# zasilanie.net
KiCad netlist of a schematic drawn in Altium Designer
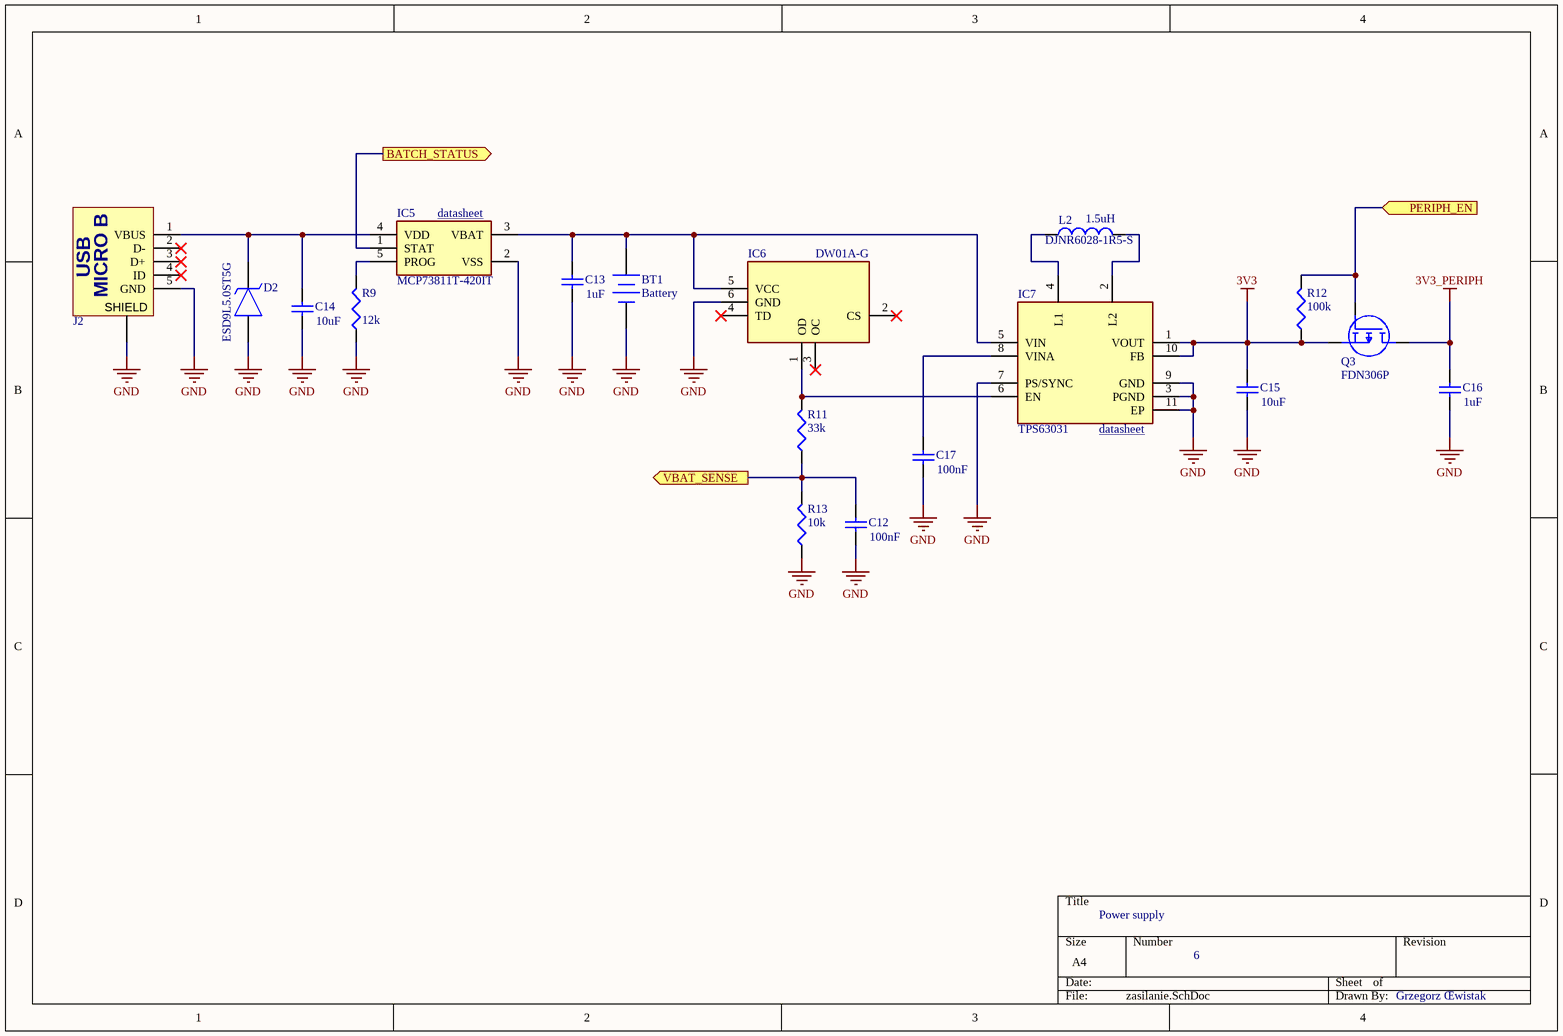
[diagram p0: zasilanie.SchDoc]

(export (version "E")
  (design (tool "Eeschema 10.0.6"))
  (components
    (comp (ref "BT1")
      (value "Battery")
      (footprint "BAT_PAD")
      (description "Multicell Battery")
      (fields (field (name "PUBLISHER") "Altium Limited"))
      (libsource (lib "Miscellaneous Devices") (part "Battery"))
    )
    (comp (ref "C12")
      (value "100nF")
      (footprint "C0805")
      (description "Capacitor")
      (fields (field (name "Comment") "Cap") (field (name "PUBLISHER") "Altium Limited"))
      (libsource (lib "Miscellaneous Devices") (part "Cap"))
    )
    (comp (ref "C13")
      (value "1uF")
      (footprint "cap-0603")
      (description "Capacitor")
      (fields (field (name "Comment") "Cap") (field (name "PUBLISHER") "Altium Limited"))
      (libsource (lib "Miscellaneous Devices") (part "Cap"))
    )
    (comp (ref "C14")
      (value "10uF")
      (footprint "cap-0603")
      (description "Capacitor")
      (fields (field (name "Comment") "Cap") (field (name "PUBLISHER") "Altium Limited"))
      (libsource (lib "Miscellaneous Devices") (part "Cap"))
    )
    (comp (ref "C15")
      (value "10uF")
      (footprint "cap-0603")
      (description "Capacitor")
      (fields (field (name "Comment") "Cap") (field (name "PUBLISHER") "Altium Limited"))
      (libsource (lib "Miscellaneous Devices") (part "Cap"))
    )
    (comp (ref "C16")
      (value "1uF")
      (footprint "cap-0603")
      (description "Capacitor")
      (fields (field (name "Comment") "Cap") (field (name "PUBLISHER") "Altium Limited"))
      (libsource (lib "Miscellaneous Devices") (part "Cap"))
    )
    (comp (ref "C17")
      (value "100nF")
      (footprint "C0805")
      (description "Capacitor")
      (fields (field (name "Comment") "Cap") (field (name "PUBLISHER") "Altium Limited"))
      (libsource (lib "Miscellaneous Devices") (part "Cap"))
    )
    (comp (ref "D2")
      (value "ESD9L5.0ST5G")
      (footprint "SODFL1006X40N")
      (description "Transil")
      (fields (field (name "MOUSER PART NUMBER") "863-ESD9L5.0ST5G"))
      (libsource (lib "lib") (part "ESD9L5.0ST5G"))
    )
    (comp (ref "IC5")
      (value "MCP73811T-420IT")
      (footprint "SOT95P270X145-5N")
      (description "Integrated Circuit")
      (fields
        (field (name "MANUFACTURER_PART_NUMBER") "MCP73831T-5ACI/OT")
        (field (name "MOUSER PART NUMBER") "579-MCP73831T5ACIOT")
      )
      (libsource (lib "lib") (part "MCP73831T"))
    )
    (comp (ref "IC6")
      (value "DW01A-G")
      (footprint "SOT95P280X135-6N")
      (description "Integrated Circuit")
      (libsource (lib "lib") (part "DW01A-G"))
    )
    (comp (ref "IC7")
      (value "TPS63031")
      (footprint "SON50P250X250X80-11N-D")
      (description "TPS63031 buck-boost 3v3")
      (fields
        (field (name "MANUFACTURER_PART_NUMBER") "TPS63031DSKT")
        (field (name "MOUSER PART NUMBER") "595-TPS63031DSKT")
      )
      (libsource (lib "lib") (part "TPS63031DSKT"))
    )
    (comp (ref "J2")
      (value "Micro USB")
      (footprint "101181930001LF")
      (description "model 10118193-0001LF amphenol")
      (fields
        (field (name "MANUFACTURER_PART_NUMBER") "10118193-0001LF")
        (field (name "MOUSER PART NUMBER") "649-10118193-0001LF")
      )
      (libsource (lib "lib") (part "USB-10118193-0001LF"))
    )
    (comp (ref "L2")
      (value "DJNR6028-1R5-S")
      (footprint "DJNR6028-1R5-S")
      (fields (field (name "ALTIUM_VALUE") "1.5uH") (field (name "PUBLISHER") "Altium Limited"))
      (libsource (lib "Miscellaneous Devices") (part "Inductor"))
    )
    (comp (ref "Q3")
      (value "FDN306P")
      (footprint "SOT95P237X112-3N")
      (description "MOSFET (P-Channel)")
      (fields (field (name "MOUSER PART NUMBER") "512-FDN306P"))
      (libsource (lib "lib") (part "FDN306P"))
    )
    (comp (ref "R9")
      (value "12k")
      (footprint "R0603")
      (description "Resistor")
      (fields (field (name "Comment") "Res3") (field (name "PUBLISHER") "Altium Limited"))
      (libsource (lib "Miscellaneous Devices") (part "Res3"))
    )
    (comp (ref "R11")
      (value "33k")
      (footprint "R0603")
      (description "Resistor")
      (fields (field (name "Comment") "Res3") (field (name "PUBLISHER") "Altium Limited"))
      (libsource (lib "Miscellaneous Devices") (part "Res3"))
    )
    (comp (ref "R12")
      (value "100k")
      (footprint "R0603")
      (description "Resistor")
      (fields (field (name "Comment") "Res3") (field (name "PUBLISHER") "Altium Limited"))
      (libsource (lib "Miscellaneous Devices") (part "Res3"))
    )
    (comp (ref "R13")
      (value "10k")
      (footprint "R0603")
      (description "Resistor")
      (fields (field (name "Comment") "Res3") (field (name "PUBLISHER") "Altium Limited"))
      (libsource (lib "Miscellaneous Devices") (part "Res3"))
    )
  )
  (nets
    (net (code "1") (name "/BATCH_STATUS") (class "Default")
      (node (ref "IC5") (pin "1") (pinfunction "STAT_1") (pintype "passive"))
    )
    (net (code "2") (name "/PERIPH_EN") (class "Default")
      (node (ref "Q3") (pin "1") (pinfunction "G_1") (pintype "passive"))
      (node (ref "R12") (pin "1") (pinfunction "1_1") (pintype "passive"))
    )
    (net (code "3") (name "/VBAT_SENSE") (class "Default")
      (node (ref "C12") (pin "2") (pinfunction "2_2") (pintype "passive"))
      (node (ref "R11") (pin "2") (pinfunction "2_2") (pintype "passive"))
      (node (ref "R13") (pin "1") (pinfunction "1_1") (pintype "passive"))
    )
    (net (code "4") (name "3V3") (class "Default")
      (node (ref "C15") (pin "2") (pinfunction "2_2") (pintype "passive"))
      (node (ref "IC7") (pin "1") (pinfunction "VOUT_1") (pintype "passive"))
      (node (ref "IC7") (pin "10") (pinfunction "FB_10") (pintype "passive"))
      (node (ref "Q3") (pin "2") (pinfunction "S_2") (pintype "passive"))
      (node (ref "R12") (pin "2") (pinfunction "2_2") (pintype "passive"))
    )
    (net (code "5") (name "3V3_PERIPH") (class "Default")
      (node (ref "C16") (pin "2") (pinfunction "2_2") (pintype "passive"))
      (node (ref "Q3") (pin "3") (pinfunction "D_3") (pintype "passive"))
    )
    (net (code "6") (name "GND") (class "Default")
      (node (ref "BT1") (pin "2") (pinfunction "-_2") (pintype "passive"))
      (node (ref "C12") (pin "1") (pinfunction "1_1") (pintype "passive"))
      (node (ref "C13") (pin "1") (pinfunction "1_1") (pintype "passive"))
      (node (ref "C14") (pin "1") (pinfunction "1_1") (pintype "passive"))
      (node (ref "C15") (pin "1") (pinfunction "1_1") (pintype "passive"))
      (node (ref "C16") (pin "1") (pinfunction "1_1") (pintype "passive"))
      (node (ref "C17") (pin "1") (pinfunction "1_1") (pintype "passive"))
      (node (ref "D2") (pin "2") (pinfunction "A_2") (pintype "passive"))
      (node (ref "IC5") (pin "2") (pinfunction "VSS_2") (pintype "passive"))
      (node (ref "IC6") (pin "6") (pinfunction "GND_6") (pintype "passive"))
      (node (ref "IC7") (pin "11") (pinfunction "EP_11") (pintype "passive"))
      (node (ref "IC7") (pin "3") (pinfunction "PGND_3") (pintype "passive"))
      (node (ref "IC7") (pin "7") (pinfunction "PS/SYNC_7") (pintype "passive"))
      (node (ref "IC7") (pin "9") (pinfunction "GND_9") (pintype "passive"))
      (node (ref "J2") (pin "5") (pinfunction "GND_5") (pintype "passive"))
      (node (ref "J2") (pin "6") (pinfunction "SHIELD_6") (pintype "passive"))
      (node (ref "R13") (pin "2") (pinfunction "2_2") (pintype "passive"))
      (node (ref "R9") (pin "1") (pinfunction "1_1") (pintype "passive"))
    )
    (net (code "7") (name "Net-(BT1-+)") (class "Default")
      (node (ref "BT1") (pin "1") (pinfunction "+_1") (pintype "passive"))
      (node (ref "C13") (pin "2") (pinfunction "2_2") (pintype "passive"))
      (node (ref "IC5") (pin "3") (pinfunction "VBAT_3") (pintype "passive"))
      (node (ref "IC6") (pin "5") (pinfunction "VCC_5") (pintype "passive"))
      (node (ref "IC7") (pin "5") (pinfunction "VIN_5") (pintype "passive"))
    )
    (net (code "8") (name "Net-(D2-K)") (class "Default")
      (node (ref "C14") (pin "2") (pinfunction "2_2") (pintype "passive"))
      (node (ref "D2") (pin "1") (pinfunction "K_1") (pintype "passive"))
      (node (ref "IC5") (pin "4") (pinfunction "VDD_4") (pintype "passive"))
      (node (ref "J2") (pin "1") (pinfunction "VBUS_1") (pintype "passive"))
    )
    (net (code "9") (name "Net-(IC5-PROG)") (class "Default")
      (node (ref "IC5") (pin "5") (pinfunction "PROG_5") (pintype "passive"))
      (node (ref "R9") (pin "2") (pinfunction "2_2") (pintype "passive"))
    )
    (net (code "10") (name "Net-(IC6-OD)") (class "Default")
      (node (ref "IC6") (pin "1") (pinfunction "OD_1") (pintype "passive"))
      (node (ref "IC7") (pin "6") (pinfunction "EN_6") (pintype "passive"))
      (node (ref "R11") (pin "1") (pinfunction "1_1") (pintype "passive"))
    )
    (net (code "11") (name "Net-(IC7-L1)") (class "Default")
      (node (ref "IC7") (pin "4") (pinfunction "L1_4") (pintype "passive"))
      (node (ref "L2") (pin "1") (pinfunction "1_1") (pintype "passive"))
    )
    (net (code "12") (name "Net-(IC7-L2)") (class "Default")
      (node (ref "IC7") (pin "2") (pinfunction "L2_2") (pintype "passive"))
      (node (ref "L2") (pin "2") (pinfunction "2_2") (pintype "passive"))
    )
    (net (code "13") (name "Net-(IC7-VINA)") (class "Default")
      (node (ref "C17") (pin "2") (pinfunction "2_2") (pintype "passive"))
      (node (ref "IC7") (pin "8") (pinfunction "VINA_8") (pintype "passive"))
    )
    (net (code "14") (name "unconnected-(IC6-CS-Pad2)") (class "Default")
      (node (ref "IC6") (pin "2") (pinfunction "CS_2") (pintype "passive+no_connect"))
    )
    (net (code "15") (name "unconnected-(IC6-OC-Pad3)") (class "Default")
      (node (ref "IC6") (pin "3") (pinfunction "OC_3") (pintype "passive+no_connect"))
    )
    (net (code "16") (name "unconnected-(IC6-TD-Pad4)") (class "Default")
      (node (ref "IC6") (pin "4") (pinfunction "TD_4") (pintype "passive+no_connect"))
    )
    (net (code "17") (name "unconnected-(J2-D+-Pad3)") (class "Default")
      (node (ref "J2") (pin "3") (pinfunction "D+_3") (pintype "passive+no_connect"))
    )
    (net (code "18") (name "unconnected-(J2-D--Pad2)") (class "Default")
      (node (ref "J2") (pin "2") (pinfunction "D-_2") (pintype "passive+no_connect"))
    )
    (net (code "19") (name "unconnected-(J2-ID-Pad4)") (class "Default")
      (node (ref "J2") (pin "4") (pinfunction "ID_4") (pintype "passive+no_connect"))
    )
  )
)
